# BD0004_1_Tester.net
KiCad netlist of a schematic drawn in EAGLE
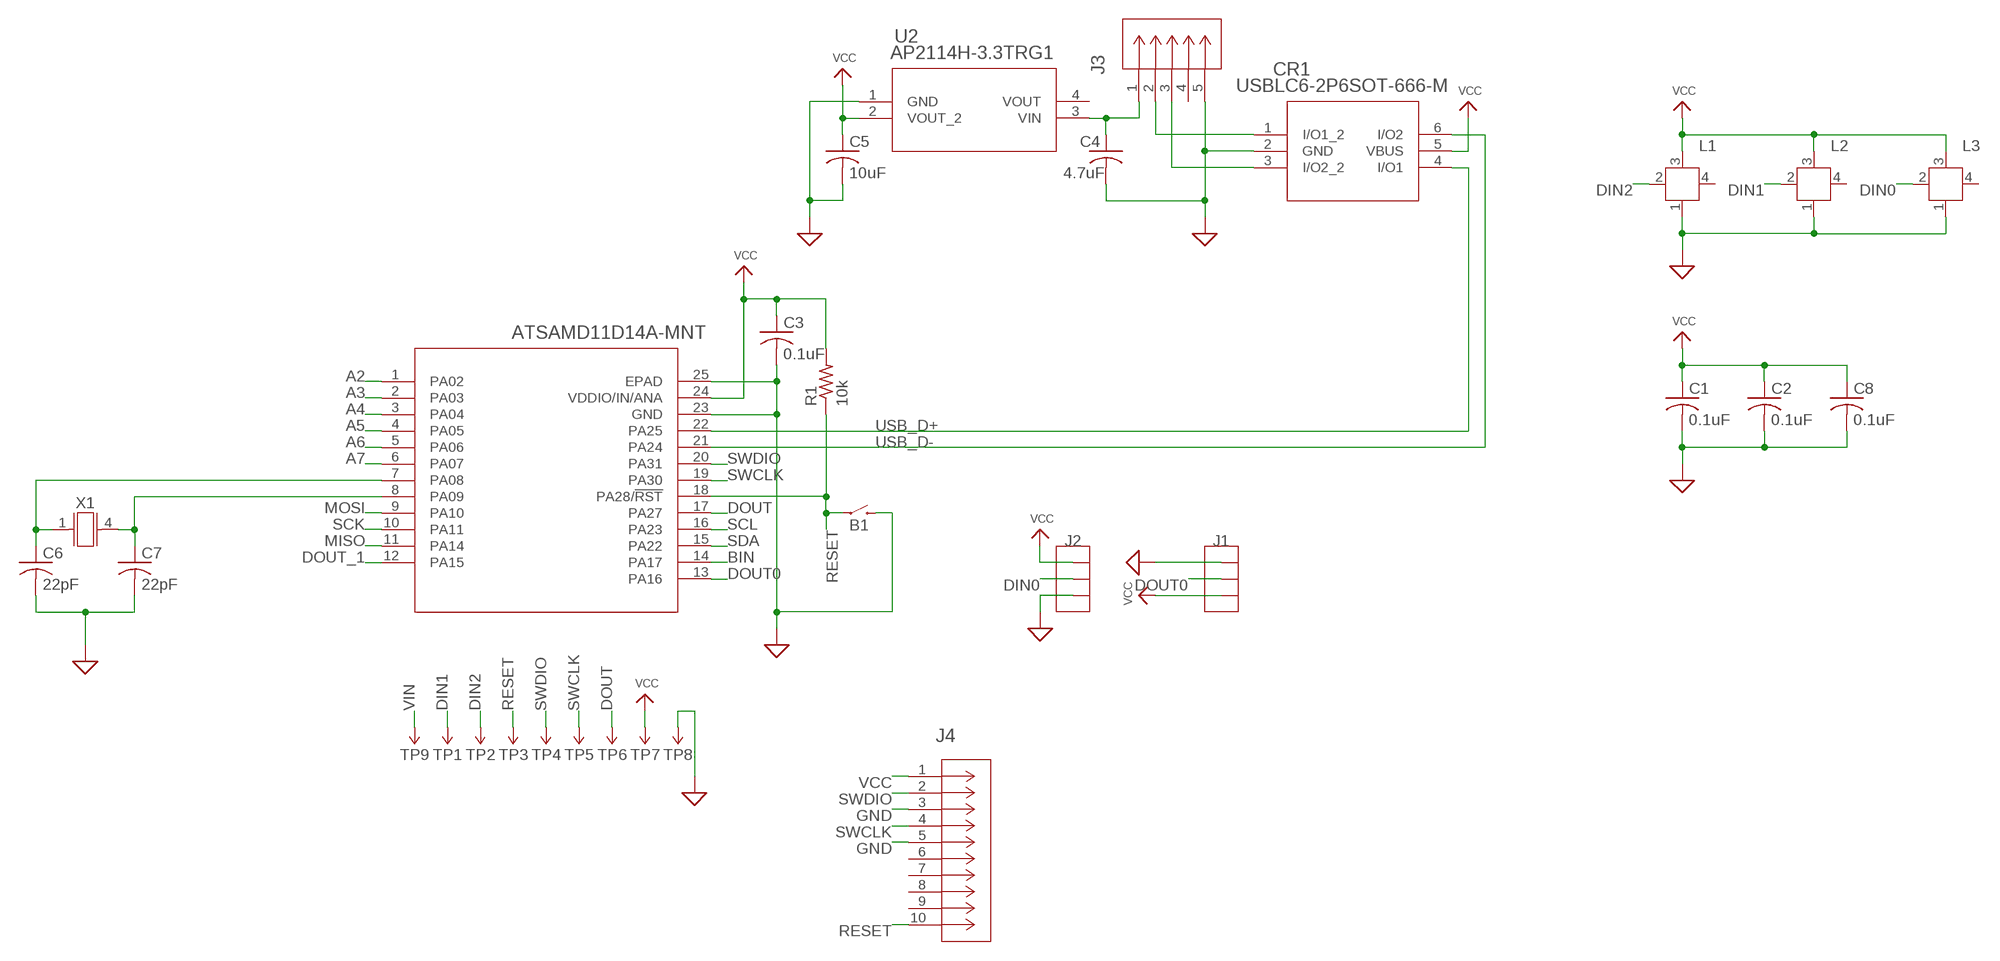
[diagram p0: schematic, sheet 1]

(export (version "E")
  (design (tool "Eeschema 10.0.6"))
  (components
    (comp (ref "B1")
      (value "EVQ-P7A01P")
      (footprint "eagle-import:4-SMD_BUTTON")
      (libsource (lib "eagle-import") (part "EVQ-P7A01P"))
    )
    (comp (ref "C1")
      (value "0.1uF")
      (footprint "eagle-import:C0402")
      (libsource (lib "eagle-import") (part "C-USC0402"))
    )
    (comp (ref "C2")
      (value "0.1uF")
      (footprint "eagle-import:C0402")
      (libsource (lib "eagle-import") (part "C-USC0402"))
    )
    (comp (ref "C3")
      (value "0.1uF")
      (footprint "eagle-import:C0402")
      (libsource (lib "eagle-import") (part "C-USC0402"))
    )
    (comp (ref "C4")
      (value "4.7uF")
      (footprint "eagle-import:C0805")
      (libsource (lib "eagle-import") (part "C-USC0805"))
    )
    (comp (ref "C5")
      (value "10uF")
      (footprint "eagle-import:C0805")
      (libsource (lib "eagle-import") (part "C-USC0805"))
    )
    (comp (ref "C6")
      (value "22pF")
      (footprint "eagle-import:C0402")
      (libsource (lib "eagle-import") (part "C-USC0402"))
    )
    (comp (ref "C7")
      (value "22pF")
      (footprint "eagle-import:C0402")
      (libsource (lib "eagle-import") (part "C-USC0402"))
    )
    (comp (ref "C8")
      (value "0.1uF")
      (footprint "eagle-import:C0402")
      (libsource (lib "eagle-import") (part "C-USC0402"))
    )
    (comp (ref "CR1")
      (value "USBLC6-2P6SOT-666-M")
      (footprint "eagle-import:SOT-666-M")
      (fields (field (name "MANUFACTURER_PART_NUMBER") "USBLC6-2P6"))
      (libsource (lib "eagle-import") (part "USBLC6-2P6SOT-666-M"))
    )
    (comp (ref "J1")
      (value "HEADER_1X3MALE")
      (footprint "eagle-import:M3SMD")
      (libsource (lib "eagle-import") (part "HEADER_1X3MALE"))
    )
    (comp (ref "J2")
      (value "HEADER_1X3FEMALE")
      (footprint "eagle-import:F3SMD")
      (libsource (lib "eagle-import") (part "HEADER_1X3FEMALE"))
    )
    (comp (ref "J3")
      (value "1050171001")
      (footprint "eagle-import:CON00679_5")
      (fields (field (name "COPYRIGHT") "Copyright (C) 2016 Accelerated Designs. All rights reserved"))
      (libsource (lib "eagle-import") (part "1050171001"))
    )
    (comp (ref "J4")
      (value "20021121-00010C4LF")
      (footprint "eagle-import:CONN_00010C4LF")
      (fields (field (name "COPYRIGHT") "Copyright (C) 2018 Accelerated Designs. All rights reserved"))
      (libsource (lib "eagle-import") (part "20021121-00010C4LF"))
    )
    (comp (ref "L1")
      (value "WS2812B")
      (footprint "eagle-import:SK6812")
      (libsource (lib "eagle-import") (part "WS2812B"))
    )
    (comp (ref "L2")
      (value "WS2812B")
      (footprint "eagle-import:SK6812")
      (libsource (lib "eagle-import") (part "WS2812B"))
    )
    (comp (ref "L3")
      (value "WS2812B")
      (footprint "eagle-import:SK6812")
      (libsource (lib "eagle-import") (part "WS2812B"))
    )
    (comp (ref "R1")
      (value "10k")
      (footprint "eagle-import:R0402")
      (libsource (lib "eagle-import") (part "R-US_R0402"))
    )
    (comp (ref "TP1")
      (value "POGO")
      (footprint "eagle-import:R-1-CR")
      (libsource (lib "eagle-import") (part "POGO"))
    )
    (comp (ref "TP2")
      (value "POGO")
      (footprint "eagle-import:R-1-CR")
      (libsource (lib "eagle-import") (part "POGO"))
    )
    (comp (ref "TP3")
      (value "POGO")
      (footprint "eagle-import:R-1-CR")
      (libsource (lib "eagle-import") (part "POGO"))
    )
    (comp (ref "TP4")
      (value "POGO")
      (footprint "eagle-import:R-1-CR")
      (libsource (lib "eagle-import") (part "POGO"))
    )
    (comp (ref "TP5")
      (value "POGO")
      (footprint "eagle-import:R-1-CR")
      (libsource (lib "eagle-import") (part "POGO"))
    )
    (comp (ref "TP6")
      (value "POGO")
      (footprint "eagle-import:R-1-CR")
      (libsource (lib "eagle-import") (part "POGO"))
    )
    (comp (ref "TP7")
      (value "POGO")
      (footprint "eagle-import:R-1-CR")
      (libsource (lib "eagle-import") (part "POGO"))
    )
    (comp (ref "TP8")
      (value "POGO")
      (footprint "eagle-import:R-1-CR")
      (libsource (lib "eagle-import") (part "POGO"))
    )
    (comp (ref "TP9")
      (value "POGO")
      (footprint "eagle-import:R-1-CR")
      (libsource (lib "eagle-import") (part "POGO"))
    )
    (comp (ref "U1")
      (value "ATSAMD11D14A-MNT")
      (footprint "eagle-import:QFN24_4X4MC")
      (fields (field (name "COPYRIGHT") "Copyright (C) 2018 Accelerated Designs. All rights reserved"))
      (libsource (lib "eagle-import") (part "ATSAMD11D14A-MNT"))
    )
    (comp (ref "U2")
      (value "AP2114H-3.3TRG1")
      (footprint "eagle-import:SOT-223")
      (libsource (lib "eagle-import") (part "AP2114H-3.3TRG1"))
    )
    (comp (ref "X1")
      (value "MC-146-32.7680JKA-A0:ROHS")
      (footprint "eagle-import:4-SMD_FLAT_LEADS")
      (libsource (lib "eagle-import") (part "MC-146-32.7680JKA-A0{colon}ROHS"))
    )
  )
  (nets
    (net (code "1") (name "/A2") (class "Default")
      (node (ref "U1") (pin "1") (pinfunction "PA02_1") (pintype "bidirectional"))
    )
    (net (code "2") (name "/A3") (class "Default")
      (node (ref "U1") (pin "2") (pinfunction "PA03_2") (pintype "bidirectional"))
    )
    (net (code "3") (name "/A4") (class "Default")
      (node (ref "U1") (pin "3") (pinfunction "PA04_3") (pintype "bidirectional"))
    )
    (net (code "4") (name "/A5") (class "Default")
      (node (ref "U1") (pin "4") (pinfunction "PA05_4") (pintype "bidirectional"))
    )
    (net (code "5") (name "/A6") (class "Default")
      (node (ref "U1") (pin "5") (pinfunction "PA06_5") (pintype "bidirectional"))
    )
    (net (code "6") (name "/A7") (class "Default")
      (node (ref "U1") (pin "6") (pinfunction "PA07_6") (pintype "bidirectional"))
    )
    (net (code "7") (name "/BIN") (class "Default")
      (node (ref "U1") (pin "14") (pinfunction "PA17_14") (pintype "bidirectional"))
    )
    (net (code "8") (name "/DIN0") (class "Default")
      (node (ref "J2") (pin "2A") (pinfunction "P$2_2A") (pintype "bidirectional"))
      (node (ref "J2") (pin "2B") (pinfunction "P$2_2B") (pintype "bidirectional"))
      (node (ref "L3") (pin "2") (pinfunction "DIN_2") (pintype "bidirectional"))
    )
    (net (code "9") (name "/DIN1") (class "Default")
      (node (ref "L2") (pin "2") (pinfunction "DIN_2") (pintype "bidirectional"))
      (node (ref "TP1") (pin "P$1") (pinfunction "P$1_P$1") (pintype "bidirectional"))
    )
    (net (code "10") (name "/DIN2") (class "Default")
      (node (ref "L1") (pin "2") (pinfunction "DIN_2") (pintype "bidirectional"))
      (node (ref "TP2") (pin "P$1") (pinfunction "P$1_P$1") (pintype "bidirectional"))
    )
    (net (code "11") (name "/DOUT") (class "Default")
      (node (ref "TP6") (pin "P$1") (pinfunction "P$1_P$1") (pintype "bidirectional"))
      (node (ref "U1") (pin "17") (pinfunction "PA27_17") (pintype "bidirectional"))
    )
    (net (code "12") (name "/DOUT0") (class "Default")
      (node (ref "J1") (pin "2") (pinfunction "P$2_2") (pintype "bidirectional"))
      (node (ref "U1") (pin "13") (pinfunction "PA16_13") (pintype "bidirectional"))
    )
    (net (code "13") (name "/DOUT_1") (class "Default")
      (node (ref "U1") (pin "12") (pinfunction "PA15_12") (pintype "bidirectional"))
    )
    (net (code "14") (name "/MISO") (class "Default")
      (node (ref "U1") (pin "11") (pinfunction "PA14_11") (pintype "bidirectional"))
    )
    (net (code "15") (name "/MOSI") (class "Default")
      (node (ref "U1") (pin "9") (pinfunction "PA10_9") (pintype "bidirectional"))
    )
    (net (code "16") (name "/RESET") (class "Default")
      (node (ref "B1") (pin "1A") (pinfunction "P$1_1A") (pintype "bidirectional"))
      (node (ref "B1") (pin "1B") (pinfunction "P$1_1B") (pintype "bidirectional"))
      (node (ref "J4") (pin "10") (pinfunction "10_10") (pintype "passive"))
      (node (ref "R1") (pin "1") (pinfunction "1_1") (pintype "passive"))
      (node (ref "TP3") (pin "P$1") (pinfunction "P$1_P$1") (pintype "bidirectional"))
      (node (ref "U1") (pin "18") (pinfunction "PA28/~{RST}_18") (pintype "bidirectional"))
    )
    (net (code "17") (name "/SCK") (class "Default")
      (node (ref "U1") (pin "10") (pinfunction "PA11_10") (pintype "bidirectional"))
    )
    (net (code "18") (name "/SCL") (class "Default")
      (node (ref "U1") (pin "16") (pinfunction "PA23_16") (pintype "bidirectional"))
    )
    (net (code "19") (name "/SDA") (class "Default")
      (node (ref "U1") (pin "15") (pinfunction "PA22_15") (pintype "bidirectional"))
    )
    (net (code "20") (name "/SWCLK") (class "Default")
      (node (ref "J4") (pin "4") (pinfunction "4_4") (pintype "passive"))
      (node (ref "TP5") (pin "P$1") (pinfunction "P$1_P$1") (pintype "bidirectional"))
      (node (ref "U1") (pin "19") (pinfunction "PA30_19") (pintype "bidirectional"))
    )
    (net (code "21") (name "/SWDIO") (class "Default")
      (node (ref "J4") (pin "2") (pinfunction "2_2") (pintype "passive"))
      (node (ref "TP4") (pin "P$1") (pinfunction "P$1_P$1") (pintype "bidirectional"))
      (node (ref "U1") (pin "20") (pinfunction "PA31_20") (pintype "bidirectional"))
    )
    (net (code "22") (name "/USB_D+") (class "Default")
      (node (ref "CR1") (pin "4") (pinfunction "I/O1_4") (pintype "bidirectional"))
      (node (ref "U1") (pin "22") (pinfunction "PA25_22") (pintype "bidirectional"))
    )
    (net (code "23") (name "/USB_D-") (class "Default")
      (node (ref "CR1") (pin "6") (pinfunction "I/O2_6") (pintype "bidirectional"))
      (node (ref "U1") (pin "21") (pinfunction "PA24_21") (pintype "bidirectional"))
    )
    (net (code "24") (name "/VIN") (class "Default")
      (node (ref "C4") (pin "1") (pinfunction "1_1") (pintype "passive"))
      (node (ref "J3") (pin "1") (pinfunction "1_1") (pintype "passive"))
      (node (ref "TP9") (pin "P$1") (pinfunction "P$1_P$1") (pintype "bidirectional"))
      (node (ref "U2") (pin "3") (pinfunction "VIN_3") (pintype "input"))
    )
    (net (code "25") (name "Net-(CR1-I{slash}O1_2)") (class "Default")
      (node (ref "CR1") (pin "1") (pinfunction "I/O1_2_1") (pintype "bidirectional"))
      (node (ref "J3") (pin "2") (pinfunction "2_2") (pintype "passive"))
    )
    (net (code "26") (name "Net-(CR1-I{slash}O2_2)") (class "Default")
      (node (ref "CR1") (pin "3") (pinfunction "I/O2_2_3") (pintype "bidirectional"))
      (node (ref "J3") (pin "3") (pinfunction "3_3") (pintype "passive"))
    )
    (net (code "27") (name "Net-(U1-PA08)") (class "Default")
      (node (ref "C6") (pin "1") (pinfunction "1_1") (pintype "passive"))
      (node (ref "U1") (pin "7") (pinfunction "PA08_7") (pintype "bidirectional"))
      (node (ref "X1") (pin "1") (pinfunction "P$1_1") (pintype "bidirectional"))
    )
    (net (code "28") (name "Net-(U1-PA09)") (class "Default")
      (node (ref "C7") (pin "1") (pinfunction "1_1") (pintype "passive"))
      (node (ref "U1") (pin "8") (pinfunction "PA09_8") (pintype "bidirectional"))
      (node (ref "X1") (pin "4") (pinfunction "P$2_4") (pintype "bidirectional"))
    )
    (net (code "29") (name "SUP") (class "Default")
      (node (ref "B1") (pin "2A") (pinfunction "P$2_2A") (pintype "bidirectional"))
      (node (ref "B1") (pin "2B") (pinfunction "P$2_2B") (pintype "bidirectional"))
      (node (ref "C1") (pin "2") (pinfunction "2_2") (pintype "passive"))
      (node (ref "C2") (pin "2") (pinfunction "2_2") (pintype "passive"))
      (node (ref "C3") (pin "2") (pinfunction "2_2") (pintype "passive"))
      (node (ref "C4") (pin "2") (pinfunction "2_2") (pintype "passive"))
      (node (ref "C5") (pin "2") (pinfunction "2_2") (pintype "passive"))
      (node (ref "C6") (pin "2") (pinfunction "2_2") (pintype "passive"))
      (node (ref "C7") (pin "2") (pinfunction "2_2") (pintype "passive"))
      (node (ref "C8") (pin "2") (pinfunction "2_2") (pintype "passive"))
      (node (ref "CR1") (pin "2") (pinfunction "GND_2") (pintype "power_in"))
      (node (ref "J1") (pin "1") (pinfunction "P$1_1") (pintype "bidirectional"))
      (node (ref "J2") (pin "3A") (pinfunction "P$3_3A") (pintype "bidirectional"))
      (node (ref "J2") (pin "3B") (pinfunction "P$3_3B") (pintype "bidirectional"))
      (node (ref "J3") (pin "5") (pinfunction "5_5") (pintype "passive"))
      (node (ref "J4") (pin "3") (pinfunction "3_3") (pintype "passive"))
      (node (ref "J4") (pin "5") (pinfunction "5_5") (pintype "passive"))
      (node (ref "L1") (pin "1") (pinfunction "VSS_1") (pintype "bidirectional"))
      (node (ref "L2") (pin "1") (pinfunction "VSS_1") (pintype "bidirectional"))
      (node (ref "L3") (pin "1") (pinfunction "VSS_1") (pintype "bidirectional"))
      (node (ref "TP8") (pin "P$1") (pinfunction "P$1_P$1") (pintype "bidirectional"))
      (node (ref "U1") (pin "23") (pinfunction "GND_23") (pintype "passive"))
      (node (ref "U1") (pin "25") (pinfunction "EPAD_25") (pintype "passive"))
      (node (ref "U2") (pin "1") (pinfunction "GND_1") (pintype "passive"))
    )
    (net (code "30") (name "VCC") (class "Default")
      (node (ref "C1") (pin "1") (pinfunction "1_1") (pintype "passive"))
      (node (ref "C2") (pin "1") (pinfunction "1_1") (pintype "passive"))
      (node (ref "C3") (pin "1") (pinfunction "1_1") (pintype "passive"))
      (node (ref "C5") (pin "1") (pinfunction "1_1") (pintype "passive"))
      (node (ref "C8") (pin "1") (pinfunction "1_1") (pintype "passive"))
      (node (ref "CR1") (pin "5") (pinfunction "VBUS_5") (pintype "power_in"))
      (node (ref "J1") (pin "3") (pinfunction "P$3_3") (pintype "bidirectional"))
      (node (ref "J2") (pin "1A") (pinfunction "P$1_1A") (pintype "bidirectional"))
      (node (ref "J2") (pin "1B") (pinfunction "P$1_1B") (pintype "bidirectional"))
      (node (ref "J4") (pin "1") (pinfunction "1_1") (pintype "passive"))
      (node (ref "L1") (pin "3") (pinfunction "VDD_3") (pintype "bidirectional"))
      (node (ref "L2") (pin "3") (pinfunction "VDD_3") (pintype "bidirectional"))
      (node (ref "L3") (pin "3") (pinfunction "VDD_3") (pintype "bidirectional"))
      (node (ref "R1") (pin "2") (pinfunction "2_2") (pintype "passive"))
      (node (ref "TP7") (pin "P$1") (pinfunction "P$1_P$1") (pintype "bidirectional"))
      (node (ref "U1") (pin "24") (pinfunction "VDDIO/IN/ANA_24") (pintype "power_in"))
      (node (ref "U2") (pin "2") (pinfunction "VOUT_2_2") (pintype "output"))
    )
    (net (code "31") (name "unconnected-(J3-Pad4)") (class "Default")
      (node (ref "J3") (pin "4") (pinfunction "4_4") (pintype "passive"))
    )
    (net (code "32") (name "unconnected-(J4-Pad6)") (class "Default")
      (node (ref "J4") (pin "6") (pinfunction "6_6") (pintype "passive"))
    )
    (net (code "33") (name "unconnected-(J4-Pad7)") (class "Default")
      (node (ref "J4") (pin "7") (pinfunction "7_7") (pintype "passive"))
    )
    (net (code "34") (name "unconnected-(J4-Pad8)") (class "Default")
      (node (ref "J4") (pin "8") (pinfunction "8_8") (pintype "passive"))
    )
    (net (code "35") (name "unconnected-(J4-Pad9)") (class "Default")
      (node (ref "J4") (pin "9") (pinfunction "9_9") (pintype "passive"))
    )
    (net (code "36") (name "unconnected-(L1-DOUT-Pad4)") (class "Default")
      (node (ref "L1") (pin "4") (pinfunction "DOUT_4") (pintype "bidirectional"))
    )
    (net (code "37") (name "unconnected-(L2-DOUT-Pad4)") (class "Default")
      (node (ref "L2") (pin "4") (pinfunction "DOUT_4") (pintype "bidirectional"))
    )
    (net (code "38") (name "unconnected-(L3-DOUT-Pad4)") (class "Default")
      (node (ref "L3") (pin "4") (pinfunction "DOUT_4") (pintype "bidirectional"))
    )
    (net (code "39") (name "unconnected-(U2-VOUT-Pad4)") (class "Default")
      (node (ref "U2") (pin "4") (pinfunction "VOUT_4") (pintype "output"))
    )
  )
)
